# Level_Switch.net
KiCad netlist of a schematic drawn in Altium Designer
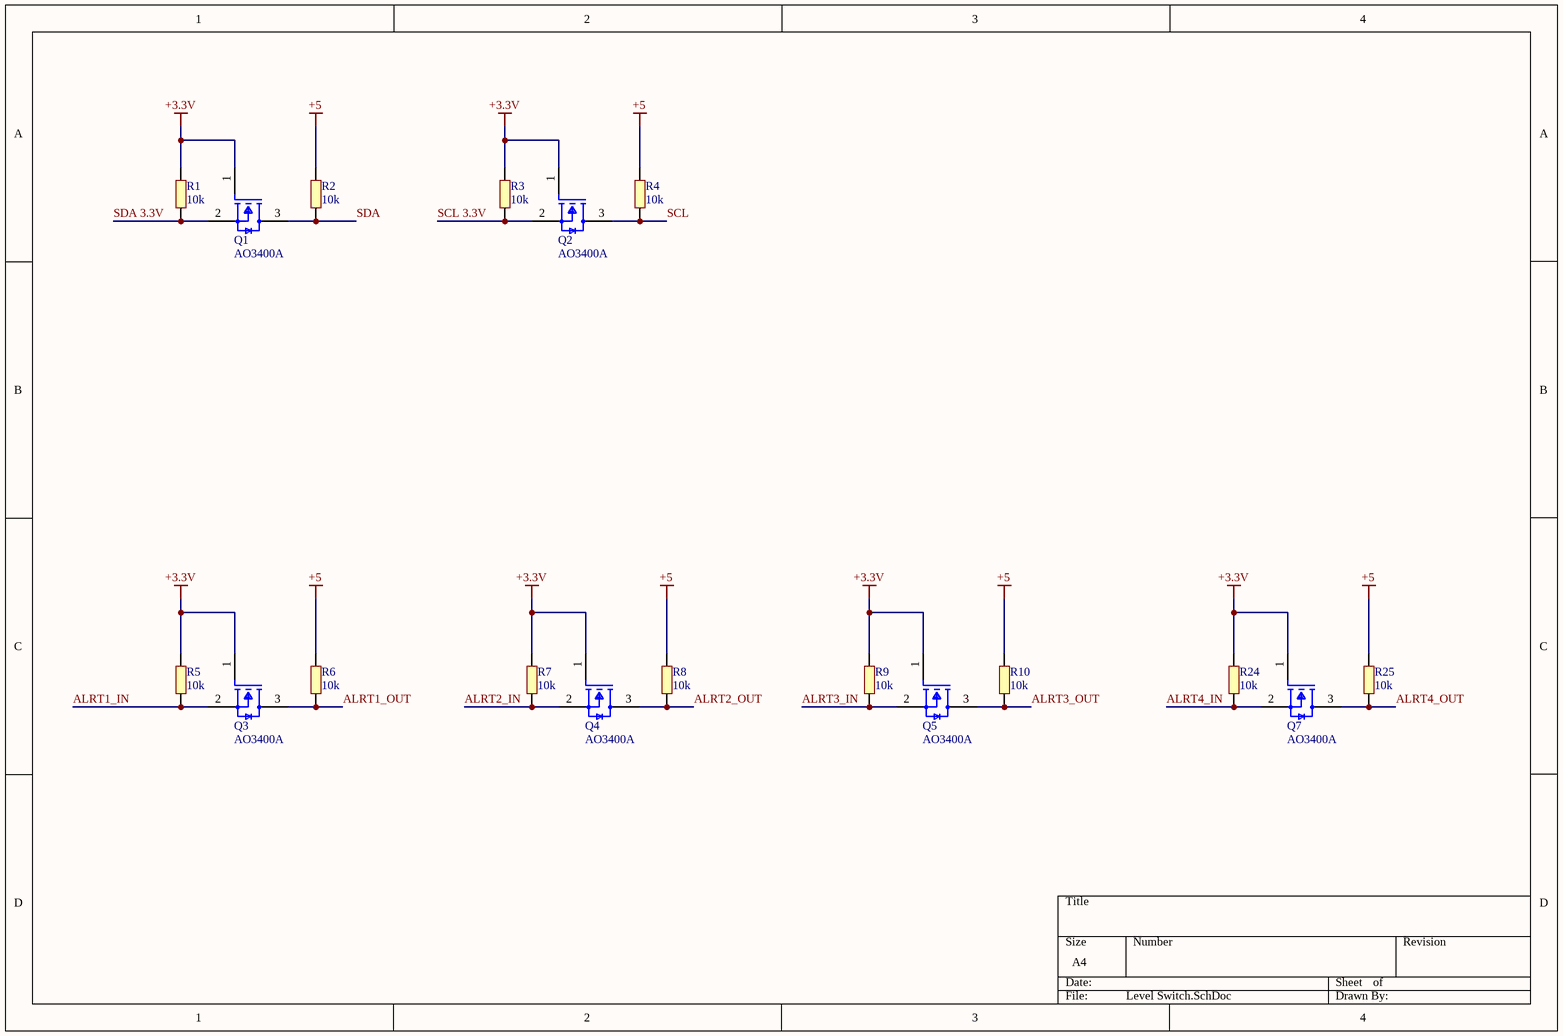
[diagram p0: Level Switch.SchDoc]

(export (version "E")
  (design (tool "Eeschema 10.0.6"))
  (components
    (comp (ref "Q1")
      (value "AO3400A")
      (footprint "FP-SOT23-MFG")
      (description "MOSFET N-CH 30V 5.7A SOT23")
      (libsource (lib "Altium Content Vault") (part "0a9ea7c96deaaede766a5b531c28de0"))
    )
    (comp (ref "Q2")
      (value "AO3400A")
      (footprint "FP-SOT23-MFG")
      (description "MOSFET N-CH 30V 5.7A SOT23")
      (libsource (lib "Altium Content Vault") (part "0a9ea7c96deaaede766a5b531c28de0"))
    )
    (comp (ref "Q3")
      (value "AO3400A")
      (footprint "FP-SOT23-MFG")
      (description "MOSFET N-CH 30V 5.7A SOT23")
      (libsource (lib "Altium Content Vault") (part "0a9ea7c96deaaede766a5b531c28de0"))
    )
    (comp (ref "Q4")
      (value "AO3400A")
      (footprint "FP-SOT23-MFG")
      (description "MOSFET N-CH 30V 5.7A SOT23")
      (libsource (lib "Altium Content Vault") (part "0a9ea7c96deaaede766a5b531c28de0"))
    )
    (comp (ref "Q5")
      (value "AO3400A")
      (footprint "FP-SOT23-MFG")
      (description "MOSFET N-CH 30V 5.7A SOT23")
      (libsource (lib "Altium Content Vault") (part "0a9ea7c96deaaede766a5b531c28de0"))
    )
    (comp (ref "Q7")
      (value "AO3400A")
      (footprint "FP-SOT23-MFG")
      (description "MOSFET N-CH 30V 5.7A SOT23")
      (libsource (lib "Altium Content Vault") (part "0a9ea7c96deaaede766a5b531c28de0"))
    )
    (comp (ref "R1")
      (value "10k")
      (footprint "Res 0603")
      (description "C25804")
      (libsource (lib "Schlib1") (part "R0603"))
    )
    (comp (ref "R2")
      (value "10k")
      (footprint "Res 0603")
      (description "C25804")
      (libsource (lib "Schlib1") (part "R0603"))
    )
    (comp (ref "R3")
      (value "10k")
      (footprint "Res 0603")
      (description "C25804")
      (libsource (lib "Schlib1") (part "R0603"))
    )
    (comp (ref "R4")
      (value "10k")
      (footprint "Res 0603")
      (description "C25804")
      (libsource (lib "Schlib1") (part "R0603"))
    )
    (comp (ref "R5")
      (value "10k")
      (footprint "Res 0603")
      (description "C25804")
      (libsource (lib "Schlib1") (part "R0603"))
    )
    (comp (ref "R6")
      (value "10k")
      (footprint "Res 0603")
      (description "C25804")
      (libsource (lib "Schlib1") (part "R0603"))
    )
    (comp (ref "R7")
      (value "10k")
      (footprint "Res 0603")
      (description "C25804")
      (libsource (lib "Schlib1") (part "R0603"))
    )
    (comp (ref "R8")
      (value "10k")
      (footprint "Res 0603")
      (description "C25804")
      (libsource (lib "Schlib1") (part "R0603"))
    )
    (comp (ref "R9")
      (value "10k")
      (footprint "Res 0603")
      (description "C25804")
      (libsource (lib "Schlib1") (part "R0603"))
    )
    (comp (ref "R10")
      (value "10k")
      (footprint "Res 0603")
      (description "C25804")
      (libsource (lib "Schlib1") (part "R0603"))
    )
    (comp (ref "R24")
      (value "10k")
      (footprint "Res 0603")
      (description "C25804")
      (libsource (lib "Schlib1") (part "R0603"))
    )
    (comp (ref "R25")
      (value "10k")
      (footprint "Res 0603")
      (description "C25804")
      (libsource (lib "Schlib1") (part "R0603"))
    )
  )
  (nets
    (net (code "1") (name "+3.3V") (class "Default")
      (node (ref "Q1") (pin "1") (pinfunction "G_1") (pintype "passive"))
      (node (ref "Q2") (pin "1") (pinfunction "G_1") (pintype "passive"))
      (node (ref "Q3") (pin "1") (pinfunction "G_1") (pintype "passive"))
      (node (ref "Q4") (pin "1") (pinfunction "G_1") (pintype "passive"))
      (node (ref "Q5") (pin "1") (pinfunction "G_1") (pintype "passive"))
      (node (ref "Q7") (pin "1") (pinfunction "G_1") (pintype "passive"))
      (node (ref "R1") (pin "2") (pinfunction "2_2") (pintype "passive"))
      (node (ref "R24") (pin "2") (pinfunction "2_2") (pintype "passive"))
      (node (ref "R3") (pin "2") (pinfunction "2_2") (pintype "passive"))
      (node (ref "R5") (pin "2") (pinfunction "2_2") (pintype "passive"))
      (node (ref "R7") (pin "2") (pinfunction "2_2") (pintype "passive"))
      (node (ref "R9") (pin "2") (pinfunction "2_2") (pintype "passive"))
    )
    (net (code "2") (name "+5") (class "Default")
      (node (ref "R10") (pin "2") (pinfunction "2_2") (pintype "passive"))
      (node (ref "R2") (pin "2") (pinfunction "2_2") (pintype "passive"))
      (node (ref "R25") (pin "2") (pinfunction "2_2") (pintype "passive"))
      (node (ref "R4") (pin "2") (pinfunction "2_2") (pintype "passive"))
      (node (ref "R6") (pin "2") (pinfunction "2_2") (pintype "passive"))
      (node (ref "R8") (pin "2") (pinfunction "2_2") (pintype "passive"))
    )
    (net (code "3") (name "/ALRT1_IN") (class "Default")
      (node (ref "Q3") (pin "2") (pinfunction "S_2") (pintype "passive"))
      (node (ref "R5") (pin "1") (pinfunction "1_1") (pintype "passive"))
    )
    (net (code "4") (name "/ALRT1_OUT") (class "Default")
      (node (ref "Q3") (pin "3") (pinfunction "D_3") (pintype "passive"))
      (node (ref "R6") (pin "1") (pinfunction "1_1") (pintype "passive"))
    )
    (net (code "5") (name "/ALRT2_IN") (class "Default")
      (node (ref "Q4") (pin "2") (pinfunction "S_2") (pintype "passive"))
      (node (ref "R7") (pin "1") (pinfunction "1_1") (pintype "passive"))
    )
    (net (code "6") (name "/ALRT2_OUT") (class "Default")
      (node (ref "Q4") (pin "3") (pinfunction "D_3") (pintype "passive"))
      (node (ref "R8") (pin "1") (pinfunction "1_1") (pintype "passive"))
    )
    (net (code "7") (name "/ALRT3_IN") (class "Default")
      (node (ref "Q5") (pin "2") (pinfunction "S_2") (pintype "passive"))
      (node (ref "R9") (pin "1") (pinfunction "1_1") (pintype "passive"))
    )
    (net (code "8") (name "/ALRT3_OUT") (class "Default")
      (node (ref "Q5") (pin "3") (pinfunction "D_3") (pintype "passive"))
      (node (ref "R10") (pin "1") (pinfunction "1_1") (pintype "passive"))
    )
    (net (code "9") (name "/ALRT4_IN") (class "Default")
      (node (ref "Q7") (pin "2") (pinfunction "S_2") (pintype "passive"))
      (node (ref "R24") (pin "1") (pinfunction "1_1") (pintype "passive"))
    )
    (net (code "10") (name "/ALRT4_OUT") (class "Default")
      (node (ref "Q7") (pin "3") (pinfunction "D_3") (pintype "passive"))
      (node (ref "R25") (pin "1") (pinfunction "1_1") (pintype "passive"))
    )
    (net (code "11") (name "/SCL") (class "Default")
      (node (ref "Q2") (pin "3") (pinfunction "D_3") (pintype "passive"))
      (node (ref "R4") (pin "1") (pinfunction "1_1") (pintype "passive"))
    )
    (net (code "12") (name "/SCL 3.3V") (class "Default")
      (node (ref "Q2") (pin "2") (pinfunction "S_2") (pintype "passive"))
      (node (ref "R3") (pin "1") (pinfunction "1_1") (pintype "passive"))
    )
    (net (code "13") (name "/SDA") (class "Default")
      (node (ref "Q1") (pin "3") (pinfunction "D_3") (pintype "passive"))
      (node (ref "R2") (pin "1") (pinfunction "1_1") (pintype "passive"))
    )
    (net (code "14") (name "/SDA 3.3V") (class "Default")
      (node (ref "Q1") (pin "2") (pinfunction "S_2") (pintype "passive"))
      (node (ref "R1") (pin "1") (pinfunction "1_1") (pintype "passive"))
    )
  )
)
